# REV13_0.net
KiCad netlist of a schematic drawn in EAGLE
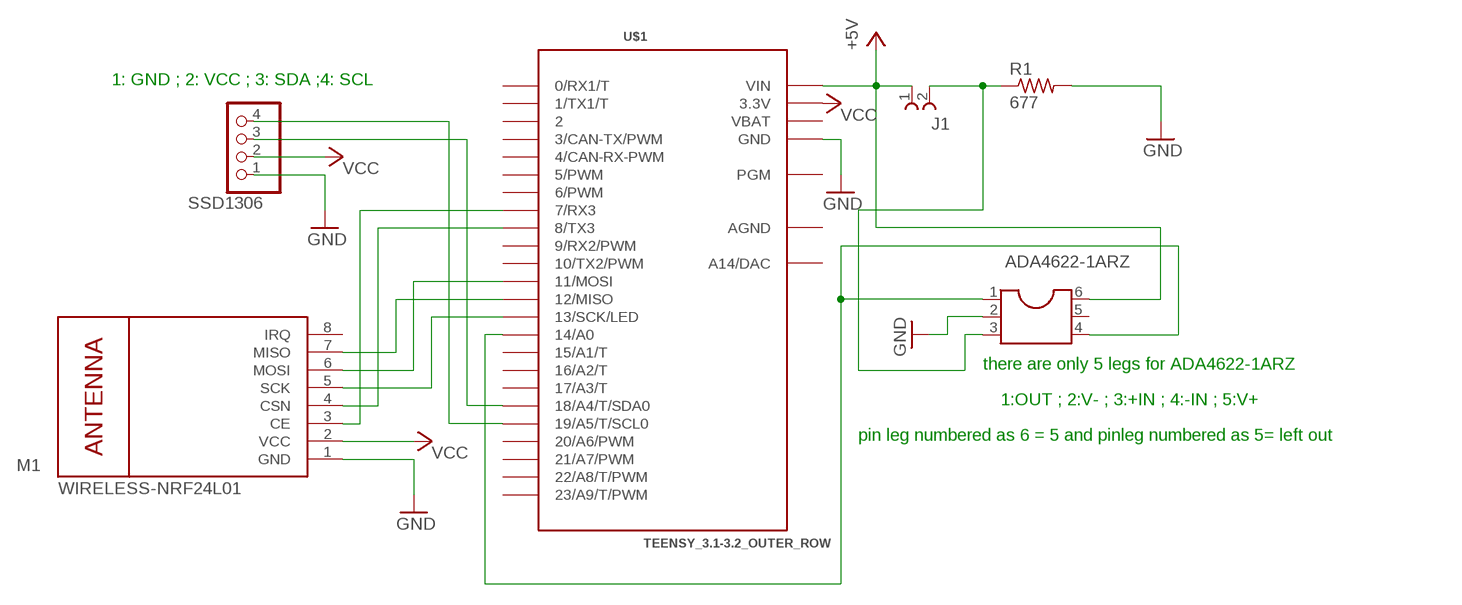
[diagram p0: schematic, sheet 1]

(export (version "E")
  (design (tool "Eeschema 10.0.6"))
  (components
    (comp (ref "ADA4622-1ARZ")
      (value "DIL6/4")
      (footprint "eagle-import:DIL06-4")
      (libsource (lib "eagle-import") (part "DIL6/4"))
    )
    (comp (ref "J1")
      (value "691214100002")
      (footprint "eagle-import:691214100002")
      (libsource (lib "eagle-import") (part "691214100002"))
    )
    (comp (ref "M1")
      (value "WIRELESS-NRF24L01")
      (footprint "eagle-import:WIRELESS-NRF24L01")
      (libsource (lib "eagle-import") (part "WIRELESS-NRF24L01"))
    )
    (comp (ref "R1")
      (value "677")
      (footprint "eagle-import:0204_5")
      (libsource (lib "eagle-import") (part "R-US_0204/5"))
    )
    (comp (ref "SSD1306")
      (value "PINHD-1X4")
      (footprint "eagle-import:1X04")
      (libsource (lib "eagle-import") (part "PINHD-1X4"))
    )
    (comp (ref "U$1")
      (value "TEENSY_3.1-3.2_OUTER_ROW")
      (footprint "eagle-import:TEENSY_3.0-3.2&LC_OUTER_ROW")
      (libsource (lib "eagle-import") (part "TEENSY_3.1-3.2_OUTER_ROW"))
    )
  )
  (nets
    (net (code "1") (name "+5V") (class "Default")
      (node (ref "ADA4622-1ARZ") (pin "6") (pinfunction "6_6") (pintype "passive"))
      (node (ref "J1") (pin "1") (pinfunction "2_1") (pintype "passive"))
      (node (ref "U$1") (pin "VIN") (pinfunction "VIN_VIN") (pintype "power_in"))
    )
    (net (code "2") (name "/AGND") (class "Default")
      (node (ref "U$1") (pin "AGND") (pinfunction "AGND_AGND") (pintype "power_in"))
    )
    (net (code "3") (name "/VBAT") (class "Default")
      (node (ref "U$1") (pin "VBAT") (pinfunction "VBAT_VBAT") (pintype "power_in"))
    )
    (net (code "4") (name "GND") (class "Default")
      (node (ref "ADA4622-1ARZ") (pin "2") (pinfunction "2_2") (pintype "passive"))
      (node (ref "M1") (pin "1") (pinfunction "GND_1") (pintype "power_in"))
      (node (ref "R1") (pin "2") (pinfunction "2_2") (pintype "passive"))
      (node (ref "SSD1306") (pin "1") (pinfunction "1_1") (pintype "passive"))
      (node (ref "U$1") (pin "GND") (pinfunction "GND_GND") (pintype "power_in"))
      (node (ref "U$1") (pin "GND1") (pinfunction "GND_GND1") (pintype "power_in"))
    )
    (net (code "5") (name "Net-(ADA4622-1ARZ-Pad1)") (class "Default")
      (node (ref "ADA4622-1ARZ") (pin "1") (pinfunction "1_1") (pintype "passive"))
      (node (ref "ADA4622-1ARZ") (pin "4") (pinfunction "4_4") (pintype "passive"))
      (node (ref "U$1") (pin "14/A0") (pinfunction "14/A0_14/A0") (pintype "bidirectional"))
    )
    (net (code "6") (name "Net-(J1-1)") (class "Default")
      (node (ref "ADA4622-1ARZ") (pin "3") (pinfunction "3_3") (pintype "passive"))
      (node (ref "J1") (pin "2") (pinfunction "1_2") (pintype "passive"))
      (node (ref "R1") (pin "1") (pinfunction "1_1") (pintype "passive"))
    )
    (net (code "7") (name "Net-(M1-CE)") (class "Default")
      (node (ref "M1") (pin "3") (pinfunction "CE_3") (pintype "bidirectional"))
      (node (ref "U$1") (pin "7") (pinfunction "7/RX3_7") (pintype "bidirectional"))
    )
    (net (code "8") (name "Net-(M1-CSN)") (class "Default")
      (node (ref "M1") (pin "4") (pinfunction "CSN_4") (pintype "bidirectional"))
      (node (ref "U$1") (pin "8") (pinfunction "8/TX3_8") (pintype "bidirectional"))
    )
    (net (code "9") (name "Net-(M1-MISO)") (class "Default")
      (node (ref "M1") (pin "7") (pinfunction "MISO_7") (pintype "bidirectional"))
      (node (ref "U$1") (pin "12") (pinfunction "12/MISO_12") (pintype "bidirectional"))
    )
    (net (code "10") (name "Net-(M1-MOSI)") (class "Default")
      (node (ref "M1") (pin "6") (pinfunction "MOSI_6") (pintype "bidirectional"))
      (node (ref "U$1") (pin "11") (pinfunction "11/MOSI_11") (pintype "bidirectional"))
    )
    (net (code "11") (name "Net-(M1-SCK)") (class "Default")
      (node (ref "M1") (pin "5") (pinfunction "SCK_5") (pintype "bidirectional"))
      (node (ref "U$1") (pin "13") (pinfunction "13/SCK/LED_13") (pintype "bidirectional"))
    )
    (net (code "12") (name "Net-(U$1-18{slash}A4{slash}T{slash}SDA0)") (class "Default")
      (node (ref "SSD1306") (pin "3") (pinfunction "3_3") (pintype "passive"))
      (node (ref "U$1") (pin "18/A4") (pinfunction "18/A4/T/SDA0_18/A4") (pintype "bidirectional"))
    )
    (net (code "13") (name "Net-(U$1-19{slash}A5{slash}T{slash}SCL0)") (class "Default")
      (node (ref "SSD1306") (pin "4") (pinfunction "4_4") (pintype "passive"))
      (node (ref "U$1") (pin "19/A5") (pinfunction "19/A5/T/SCL0_19/A5") (pintype "bidirectional"))
    )
    (net (code "14") (name "VCC") (class "Default")
      (node (ref "M1") (pin "2") (pinfunction "VCC_2") (pintype "power_in"))
      (node (ref "SSD1306") (pin "2") (pinfunction "2_2") (pintype "passive"))
      (node (ref "U$1") (pin "3.3V") (pinfunction "3.3V_3.3V") (pintype "power_in"))
      (node (ref "U$1") (pin "3.3V1") (pinfunction "3.3V_3.3V1") (pintype "power_in"))
    )
    (net (code "15") (name "unconnected-(ADA4622-1ARZ-Pad5)") (class "Default")
      (node (ref "ADA4622-1ARZ") (pin "5") (pinfunction "5_5") (pintype "passive"))
    )
    (net (code "16") (name "unconnected-(M1-IRQ-Pad8)") (class "Default")
      (node (ref "M1") (pin "8") (pinfunction "IRQ_8") (pintype "bidirectional"))
    )
    (net (code "17") (name "unconnected-(U$1-0{slash}RX1{slash}T-Pad0)") (class "Default")
      (node (ref "U$1") (pin "0") (pinfunction "0/RX1/T_0") (pintype "bidirectional"))
    )
    (net (code "18") (name "unconnected-(U$1-1{slash}TX1{slash}T-Pad1)") (class "Default")
      (node (ref "U$1") (pin "1") (pinfunction "1/TX1/T_1") (pintype "bidirectional"))
    )
    (net (code "19") (name "unconnected-(U$1-3{slash}CAN-TX{slash}PWM-Pad3)") (class "Default")
      (node (ref "U$1") (pin "3") (pinfunction "3/CAN-TX/PWM_3") (pintype "bidirectional"))
    )
    (net (code "20") (name "unconnected-(U$1-4{slash}CAN-RX-PWM-Pad4)") (class "Default")
      (node (ref "U$1") (pin "4") (pinfunction "4/CAN-RX-PWM_4") (pintype "bidirectional"))
    )
    (net (code "21") (name "unconnected-(U$1-5{slash}PWM-Pad5)") (class "Default")
      (node (ref "U$1") (pin "5") (pinfunction "5/PWM_5") (pintype "bidirectional"))
    )
    (net (code "22") (name "unconnected-(U$1-6{slash}PWM-Pad6)") (class "Default")
      (node (ref "U$1") (pin "6") (pinfunction "6/PWM_6") (pintype "bidirectional"))
    )
    (net (code "23") (name "unconnected-(U$1-9{slash}RX2{slash}PWM-Pad9)") (class "Default")
      (node (ref "U$1") (pin "9") (pinfunction "9/RX2/PWM_9") (pintype "bidirectional"))
    )
    (net (code "24") (name "unconnected-(U$1-10{slash}TX2{slash}PWM-Pad10)") (class "Default")
      (node (ref "U$1") (pin "10") (pinfunction "10/TX2/PWM_10") (pintype "bidirectional"))
    )
    (net (code "25") (name "unconnected-(U$1-15{slash}A1{slash}T-Pad15{slash}A1)") (class "Default")
      (node (ref "U$1") (pin "15/A1") (pinfunction "15/A1/T_15/A1") (pintype "bidirectional"))
    )
    (net (code "26") (name "unconnected-(U$1-16{slash}A2{slash}T-Pad16{slash}A2)") (class "Default")
      (node (ref "U$1") (pin "16/A2") (pinfunction "16/A2/T_16/A2") (pintype "bidirectional"))
    )
    (net (code "27") (name "unconnected-(U$1-17{slash}A3{slash}T-Pad17{slash}A3)") (class "Default")
      (node (ref "U$1") (pin "17/A3") (pinfunction "17/A3/T_17/A3") (pintype "bidirectional"))
    )
    (net (code "28") (name "unconnected-(U$1-20{slash}A6{slash}PWM-Pad20{slash}A6)") (class "Default")
      (node (ref "U$1") (pin "20/A6") (pinfunction "20/A6/PWM_20/A6") (pintype "bidirectional"))
    )
    (net (code "29") (name "unconnected-(U$1-21{slash}A7{slash}PWM-Pad21{slash}A7)") (class "Default")
      (node (ref "U$1") (pin "21/A7") (pinfunction "21/A7/PWM_21/A7") (pintype "bidirectional"))
    )
    (net (code "30") (name "unconnected-(U$1-22{slash}A8{slash}T{slash}PWM-Pad22{slash}A8)") (class "Default")
      (node (ref "U$1") (pin "22/A8") (pinfunction "22/A8/T/PWM_22/A8") (pintype "bidirectional"))
    )
    (net (code "31") (name "unconnected-(U$1-23{slash}A9{slash}T{slash}PWM-Pad23{slash}A9)") (class "Default")
      (node (ref "U$1") (pin "23/A9") (pinfunction "23/A9/T/PWM_23/A9") (pintype "bidirectional"))
    )
    (net (code "32") (name "unconnected-(U$1-A14{slash}DAC-PadRESET{slash}DAC)") (class "Default")
      (node (ref "U$1") (pin "RESET/DAC") (pinfunction "A14/DAC_RESET/DAC") (pintype "bidirectional"))
    )
    (net (code "33") (name "unconnected-(U$1-Pad2)") (class "Default")
      (node (ref "U$1") (pin "2") (pinfunction "2_2") (pintype "bidirectional"))
    )
    (net (code "34") (name "unconnected-(U$1-PadPGM)") (class "Default")
      (node (ref "U$1") (pin "PGM") (pinfunction "PGM_PGM") (pintype "bidirectional"))
    )
  )
)
